# FPV_GROUND_STATION_SOURCE.net
KiCad netlist of a schematic drawn in EasyEDA Pro
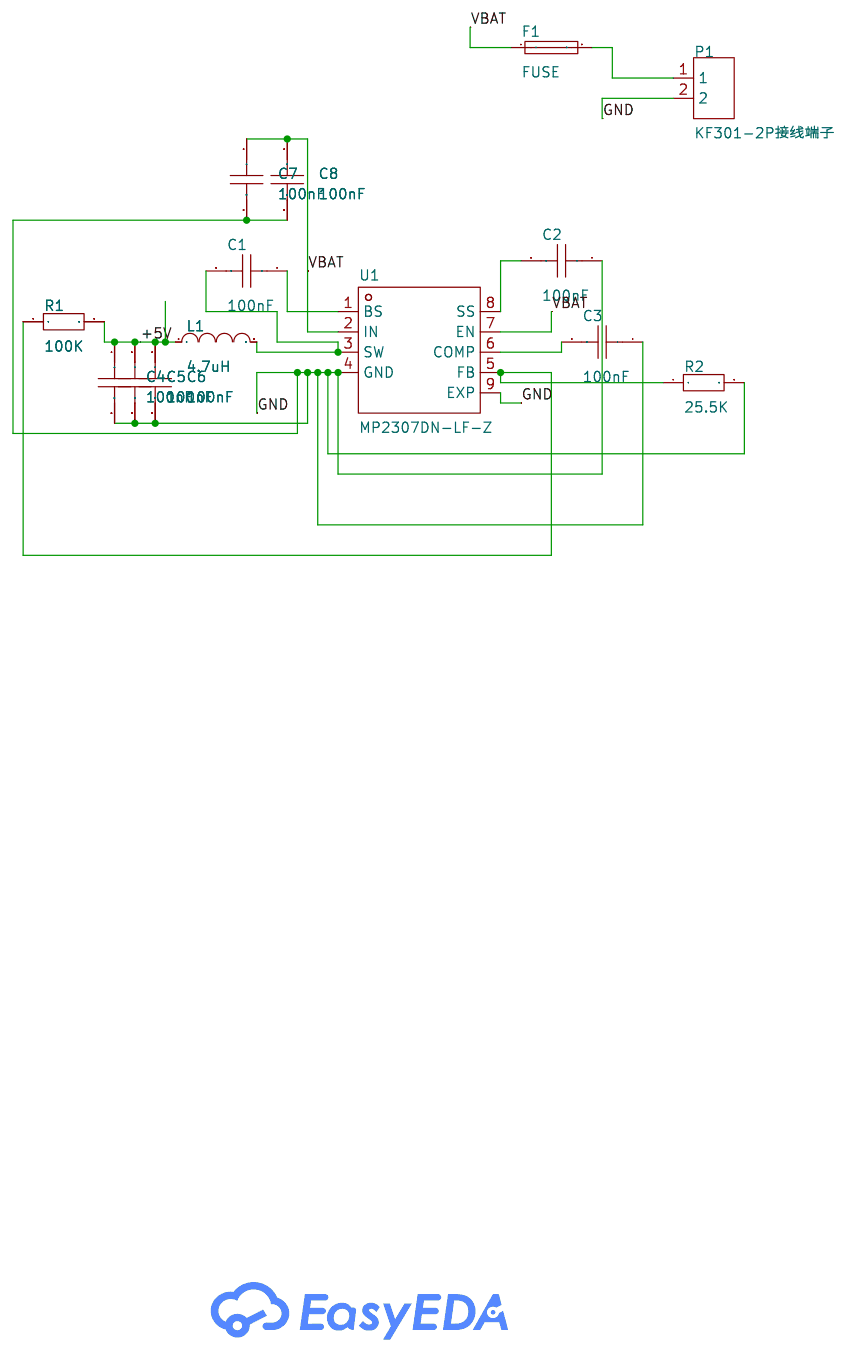
[diagram p0: POWER_BLK]
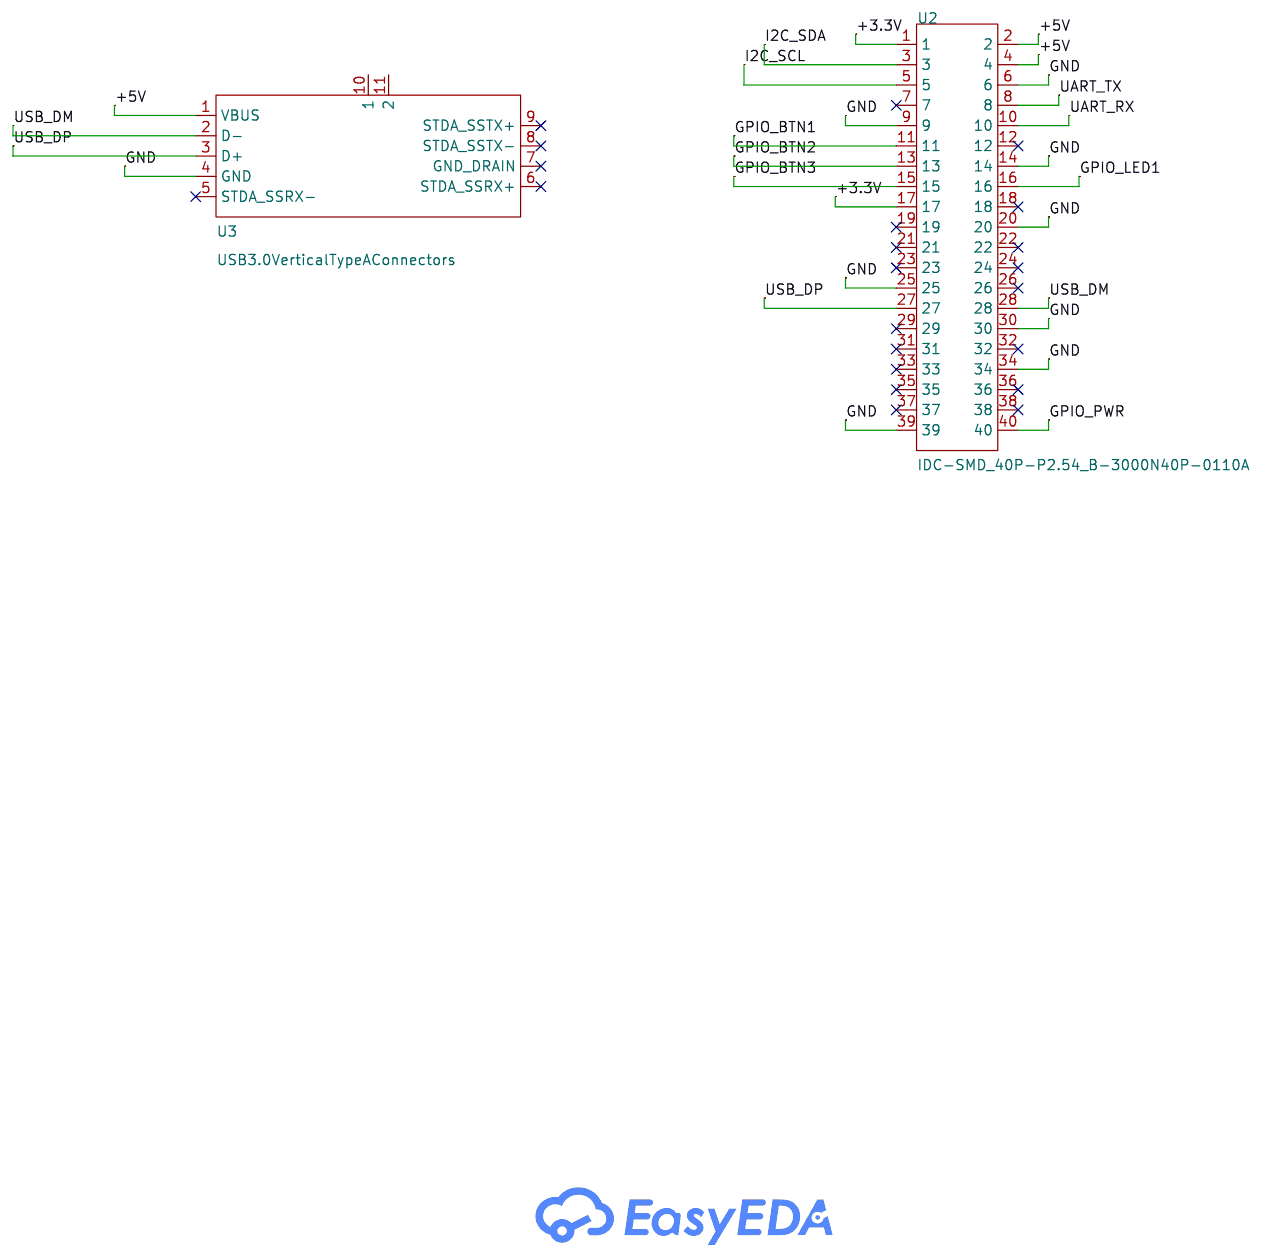
[diagram p1: GPIO header + USB-A]
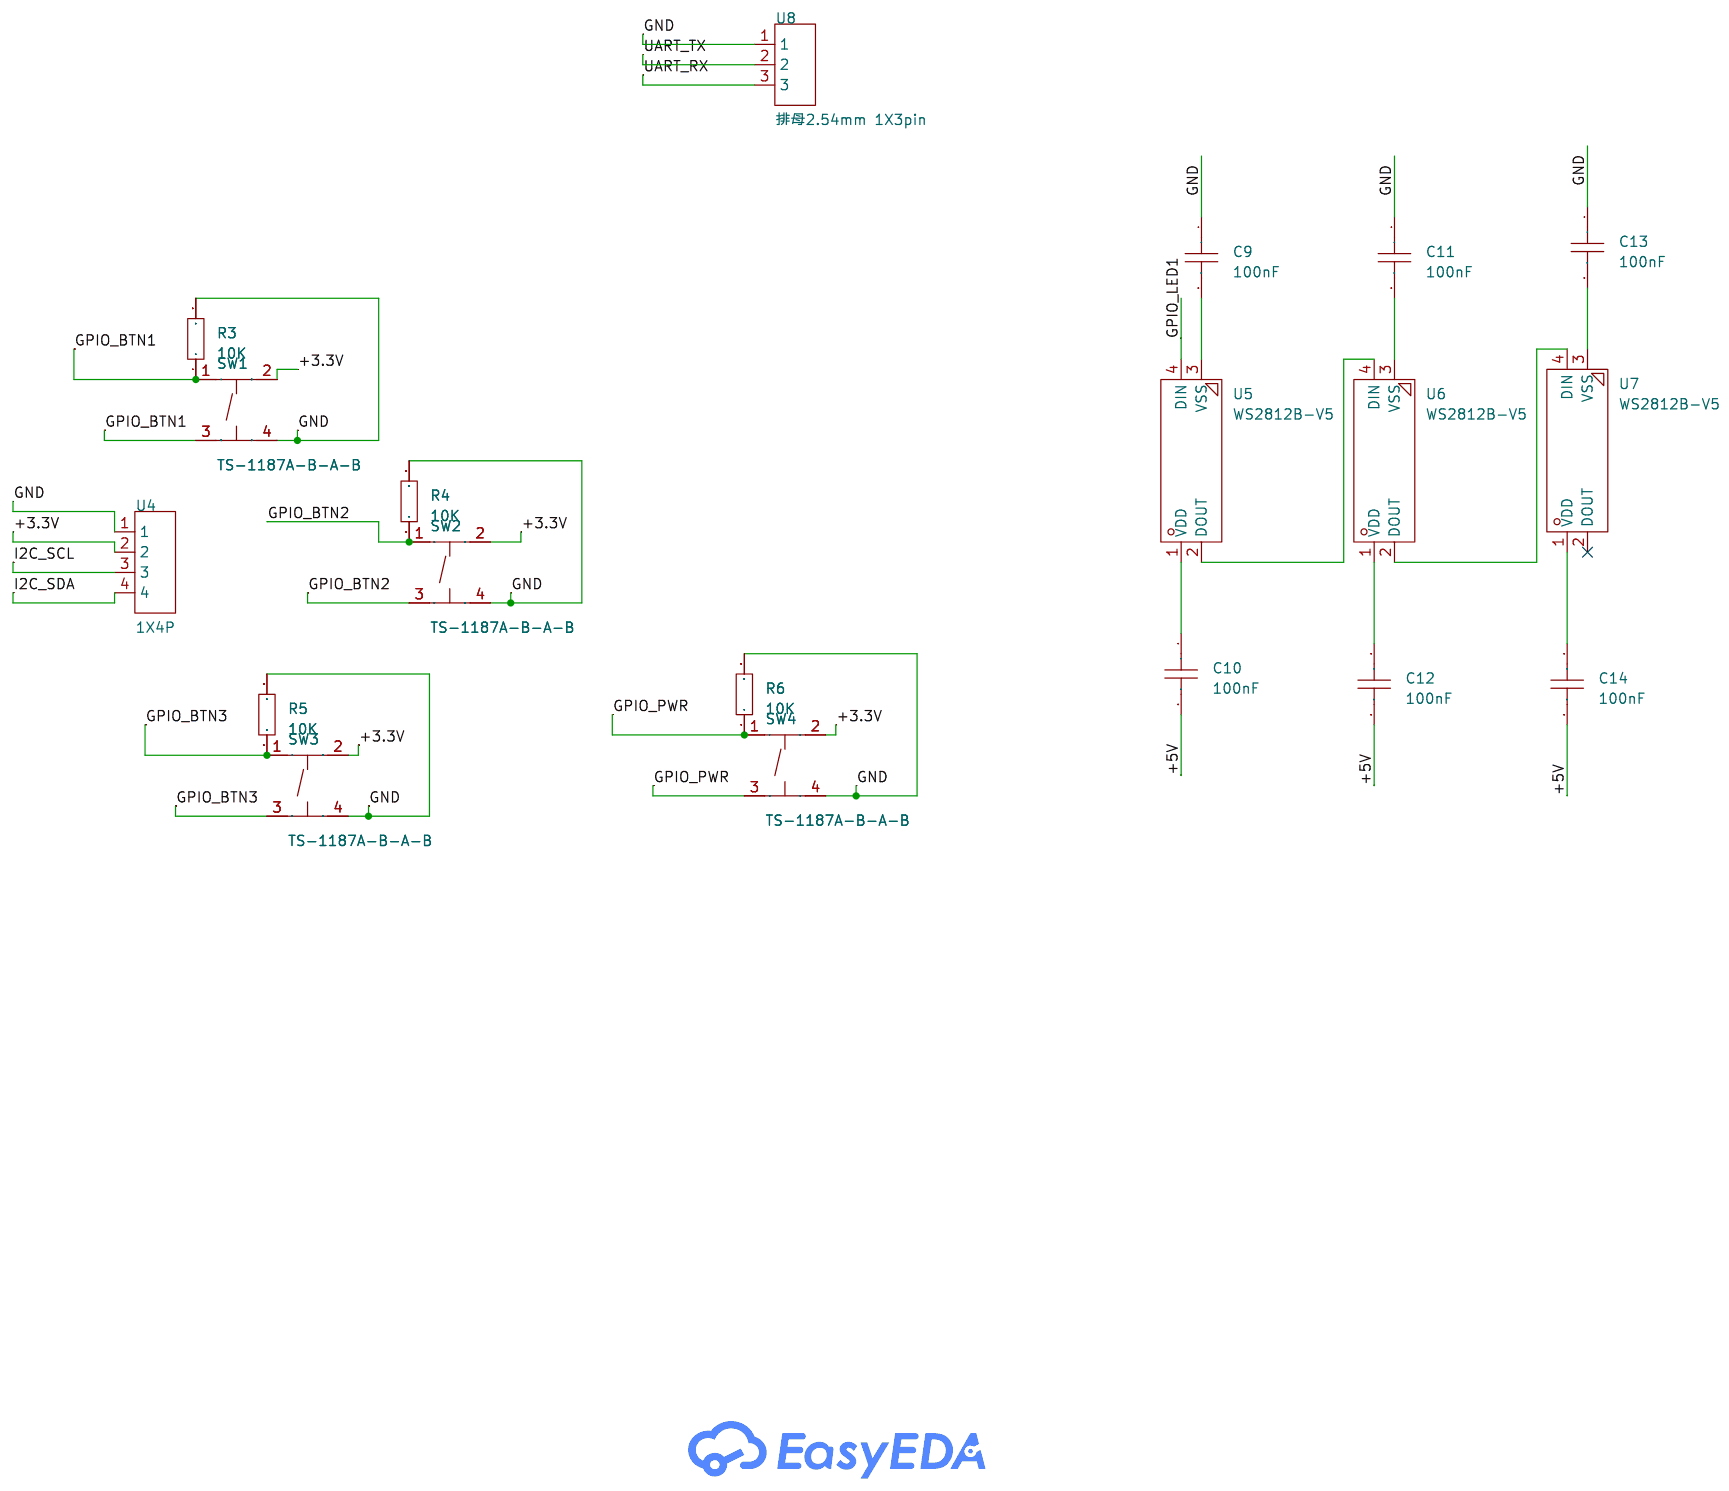
[diagram p2: LEDS AND OLED DISP]

(export (version "E")
  (design (tool "Eeschema 10.0.6"))
  (components
    (comp (ref "C1")
      (value "100nF")
      (footprint "easyedapro:C0603")
      (libsource (lib "easyedapro") (part "CAP"))
    )
    (comp (ref "C2")
      (value "100nF")
      (footprint "easyedapro:C0603")
      (libsource (lib "easyedapro") (part "CAP"))
    )
    (comp (ref "C3")
      (value "100nF")
      (footprint "easyedapro:C0603")
      (libsource (lib "easyedapro") (part "CAP"))
    )
    (comp (ref "C4")
      (value "100nF")
      (footprint "easyedapro:C0603")
      (libsource (lib "easyedapro") (part "CAP"))
    )
    (comp (ref "C5")
      (value "100nF")
      (footprint "easyedapro:C0603")
      (libsource (lib "easyedapro") (part "CAP"))
    )
    (comp (ref "C6")
      (value "100nF")
      (footprint "easyedapro:C0603")
      (libsource (lib "easyedapro") (part "CAP"))
    )
    (comp (ref "C7")
      (value "100nF")
      (footprint "easyedapro:C0603")
      (libsource (lib "easyedapro") (part "CAP"))
    )
    (comp (ref "C8")
      (value "100nF")
      (footprint "easyedapro:C0603")
      (libsource (lib "easyedapro") (part "CAP"))
    )
    (comp (ref "F1")
      (value "FUSE")
      (footprint "easyedapro:F1206")
      (libsource (lib "easyedapro") (part "FUSE"))
    )
    (comp (ref "L1")
      (value "4.7uH")
      (footprint "easyedapro:L0603")
      (libsource (lib "easyedapro") (part "电感"))
    )
    (comp (ref "P1")
      (value "KF301-2P接线端子")
      (footprint "easyedapro:CONN-TH_XY301V-A-5.0-2P")
      (libsource (lib "easyedapro") (part "KF301-2P接线端子"))
    )
    (comp (ref "R1")
      (value "100K")
      (footprint "easyedapro:R0603")
      (libsource (lib "easyedapro") (part "Res"))
    )
    (comp (ref "R2")
      (value "25.5K")
      (footprint "easyedapro:R0603")
      (libsource (lib "easyedapro") (part "Res"))
    )
    (comp (ref "U1")
      (value "MP2307DN-LF-Z")
      (footprint "easyedapro:SOP-8_L4.9-W3.9-P1.27-LS6.0-BL-EP")
      (fields (field (name "Manufacturer") "MPS(芯源)"))
      (libsource (lib "easyedapro") (part "MP2307DN-LF-Z"))
    )
    (comp (ref "U2")
      (value "IDC-SMD_40P-P2.54_B-3000N40P-0110A")
      (footprint "easyedapro:HDR-SMD_40P-P2.54-V-F-R2-C20-LS7.9")
      (libsource (lib "easyedapro") (part "IDC-SMD_40P-P2.54_B-3000N40P-0110A"))
    )
    (comp (ref "U3")
      (value "USB3.0VerticalTypeAConnectors")
      (footprint "easyedapro:USB-A-TH_C9900010398")
      (libsource (lib "easyedapro") (part "USB3.0VERTICALTYPEACONNECTORS"))
    )
    (comp (ref "C9")
      (value "100nF")
      (footprint "easyedapro:C0603")
      (libsource (lib "easyedapro") (part "CAP"))
    )
    (comp (ref "C10")
      (value "100nF")
      (footprint "easyedapro:C0603")
      (libsource (lib "easyedapro") (part "CAP"))
    )
    (comp (ref "C11")
      (value "100nF")
      (footprint "easyedapro:C0603")
      (libsource (lib "easyedapro") (part "CAP"))
    )
    (comp (ref "C12")
      (value "100nF")
      (footprint "easyedapro:C0603")
      (libsource (lib "easyedapro") (part "CAP"))
    )
    (comp (ref "C13")
      (value "100nF")
      (footprint "easyedapro:C0603")
      (libsource (lib "easyedapro") (part "CAP"))
    )
    (comp (ref "C14")
      (value "100nF")
      (footprint "easyedapro:C0603")
      (libsource (lib "easyedapro") (part "CAP"))
    )
    (comp (ref "R3") (value "10K") (footprint "easyedapro:R0603") (libsource (lib "easyedapro") (part "Res")))
    (comp (ref "R4") (value "10K") (footprint "easyedapro:R0603") (libsource (lib "easyedapro") (part "Res")))
    (comp (ref "R5") (value "10K") (footprint "easyedapro:R0603") (libsource (lib "easyedapro") (part "Res")))
    (comp (ref "R6") (value "10K") (footprint "easyedapro:R0603") (libsource (lib "easyedapro") (part "Res")))
    (comp (ref "SW1")
      (value "TS-1187A-B-A-B")
      (footprint "easyedapro:SW-SMD_4P-L5.1-W5.1-P3.70-LS6.5-TL_H1.5")
      (fields (field (name "Manufacturer") "XKB Connection(中国星坤)"))
      (libsource (lib "easyedapro") (part "TS-1187A-B-A-B"))
    )
    (comp (ref "SW2")
      (value "TS-1187A-B-A-B")
      (footprint "easyedapro:SW-SMD_4P-L5.1-W5.1-P3.70-LS6.5-TL_H1.5")
      (fields (field (name "Manufacturer") "XKB Connection(中国星坤)"))
      (libsource (lib "easyedapro") (part "TS-1187A-B-A-B"))
    )
    (comp (ref "SW3")
      (value "TS-1187A-B-A-B")
      (footprint "easyedapro:SW-SMD_4P-L5.1-W5.1-P3.70-LS6.5-TL_H1.5")
      (fields (field (name "Manufacturer") "XKB Connection(中国星坤)"))
      (libsource (lib "easyedapro") (part "TS-1187A-B-A-B"))
    )
    (comp (ref "SW4")
      (value "TS-1187A-B-A-B")
      (footprint "easyedapro:SW-SMD_4P-L5.1-W5.1-P3.70-LS6.5-TL_H1.5")
      (fields (field (name "Manufacturer") "XKB Connection(中国星坤)"))
      (libsource (lib "easyedapro") (part "TS-1187A-B-A-B"))
    )
    (comp (ref "U4")
      (value "1X4P")
      (footprint "easyedapro:CONN-TH_4P-P2.54_C9900022166")
      (libsource (lib "easyedapro") (part "1X4P"))
    )
    (comp (ref "U5")
      (value "WS2812B-V5")
      (footprint "easyedapro:LED-SMD_4P-L5.0-W5.0-TL_WS2812B-B")
      (libsource (lib "easyedapro") (part "WS2812B-V5"))
    )
    (comp (ref "U6")
      (value "WS2812B-V5")
      (footprint "easyedapro:LED-SMD_4P-L5.0-W5.0-TL_WS2812B-B")
      (libsource (lib "easyedapro") (part "WS2812B-V5"))
    )
    (comp (ref "U7")
      (value "WS2812B-V5")
      (footprint "easyedapro:LED-SMD_4P-L5.0-W5.0-TL_WS2812B-B")
      (libsource (lib "easyedapro") (part "WS2812B-V5"))
    )
    (comp (ref "U8")
      (value "排母2.54mm 1X3pin")
      (footprint "easyedapro:HDR-TH_3P-P2.54_CS-1165SDIG")
      (libsource (lib "easyedapro") (part "排母2.54MM 1X3PIN"))
    )
  )
  (nets
    (net (code "1") (name "+3.3V") (class "Default")
      (node (ref "SW1") (pin "2") (pinfunction "B_2") (pintype "unspecified"))
      (node (ref "SW2") (pin "2") (pinfunction "B_2") (pintype "unspecified"))
      (node (ref "SW3") (pin "2") (pinfunction "B_2") (pintype "unspecified"))
      (node (ref "SW4") (pin "2") (pinfunction "B_2") (pintype "unspecified"))
      (node (ref "U2") (pin "1") (pinfunction "1_1") (pintype "unspecified"))
      (node (ref "U2") (pin "17") (pinfunction "17_17") (pintype "unspecified"))
      (node (ref "U4") (pin "2") (pinfunction "2_2") (pintype "unspecified"))
    )
    (net (code "2") (name "+5V") (class "Default")
      (node (ref "C10") (pin "2") (pinfunction "2_2") (pintype "input"))
      (node (ref "C12") (pin "2") (pinfunction "2_2") (pintype "input"))
      (node (ref "C14") (pin "2") (pinfunction "2_2") (pintype "input"))
      (node (ref "C4") (pin "1") (pinfunction "1_1") (pintype "input"))
      (node (ref "C5") (pin "1") (pinfunction "1_1") (pintype "input"))
      (node (ref "C6") (pin "1") (pinfunction "1_1") (pintype "input"))
      (node (ref "L1") (pin "1") (pinfunction "1_1") (pintype "input"))
      (node (ref "R1") (pin "2") (pinfunction "2_2") (pintype "input"))
      (node (ref "U2") (pin "2") (pinfunction "2_2") (pintype "unspecified"))
      (node (ref "U2") (pin "4") (pinfunction "4_4") (pintype "unspecified"))
      (node (ref "U3") (pin "1") (pinfunction "VBUS_1") (pintype "unspecified"))
    )
    (net (code "3") (name "GND") (class "Default")
      (node (ref "C11") (pin "1") (pinfunction "1_1") (pintype "input"))
      (node (ref "C13") (pin "1") (pinfunction "1_1") (pintype "input"))
      (node (ref "C2") (pin "1") (pinfunction "1_1") (pintype "input"))
      (node (ref "C3") (pin "1") (pinfunction "1_1") (pintype "input"))
      (node (ref "C4") (pin "2") (pinfunction "2_2") (pintype "input"))
      (node (ref "C5") (pin "2") (pinfunction "2_2") (pintype "input"))
      (node (ref "C6") (pin "2") (pinfunction "2_2") (pintype "input"))
      (node (ref "C7") (pin "2") (pinfunction "2_2") (pintype "input"))
      (node (ref "C8") (pin "2") (pinfunction "2_2") (pintype "input"))
      (node (ref "C9") (pin "1") (pinfunction "1_1") (pintype "input"))
      (node (ref "P1") (pin "2") (pinfunction "2_2") (pintype "unspecified"))
      (node (ref "R2") (pin "2") (pinfunction "2_2") (pintype "input"))
      (node (ref "R3") (pin "2") (pinfunction "2_2") (pintype "input"))
      (node (ref "R4") (pin "2") (pinfunction "2_2") (pintype "input"))
      (node (ref "R5") (pin "2") (pinfunction "2_2") (pintype "input"))
      (node (ref "R6") (pin "2") (pinfunction "2_2") (pintype "input"))
      (node (ref "SW1") (pin "4") (pinfunction "D_4") (pintype "unspecified"))
      (node (ref "SW2") (pin "4") (pinfunction "D_4") (pintype "unspecified"))
      (node (ref "SW3") (pin "4") (pinfunction "D_4") (pintype "unspecified"))
      (node (ref "SW4") (pin "4") (pinfunction "D_4") (pintype "unspecified"))
      (node (ref "U1") (pin "4") (pinfunction "GND_4") (pintype "unspecified"))
      (node (ref "U1") (pin "9") (pinfunction "EXP_9") (pintype "unspecified"))
      (node (ref "U2") (pin "14") (pinfunction "14_14") (pintype "unspecified"))
      (node (ref "U2") (pin "20") (pinfunction "20_20") (pintype "unspecified"))
      (node (ref "U2") (pin "25") (pinfunction "25_25") (pintype "unspecified"))
      (node (ref "U2") (pin "30") (pinfunction "30_30") (pintype "unspecified"))
      (node (ref "U2") (pin "34") (pinfunction "34_34") (pintype "unspecified"))
      (node (ref "U2") (pin "39") (pinfunction "39_39") (pintype "unspecified"))
      (node (ref "U2") (pin "6") (pinfunction "6_6") (pintype "unspecified"))
      (node (ref "U2") (pin "9") (pinfunction "9_9") (pintype "unspecified"))
      (node (ref "U3") (pin "4") (pinfunction "GND_4") (pintype "unspecified"))
      (node (ref "U4") (pin "1") (pinfunction "1_1") (pintype "unspecified"))
      (node (ref "U8") (pin "1") (pinfunction "1_1") (pintype "unspecified"))
    )
    (net (code "4") (name "GPIO_BTN1") (class "Default")
      (node (ref "R3") (pin "1") (pinfunction "1_1") (pintype "input"))
      (node (ref "SW1") (pin "1") (pinfunction "A_1") (pintype "unspecified"))
      (node (ref "SW1") (pin "3") (pinfunction "C_3") (pintype "unspecified"))
      (node (ref "U2") (pin "11") (pinfunction "11_11") (pintype "unspecified"))
    )
    (net (code "5") (name "GPIO_BTN2") (class "Default")
      (node (ref "R4") (pin "1") (pinfunction "1_1") (pintype "input"))
      (node (ref "SW2") (pin "1") (pinfunction "A_1") (pintype "unspecified"))
      (node (ref "SW2") (pin "3") (pinfunction "C_3") (pintype "unspecified"))
      (node (ref "U2") (pin "13") (pinfunction "13_13") (pintype "unspecified"))
    )
    (net (code "6") (name "GPIO_BTN3") (class "Default")
      (node (ref "R5") (pin "1") (pinfunction "1_1") (pintype "input"))
      (node (ref "SW3") (pin "1") (pinfunction "A_1") (pintype "unspecified"))
      (node (ref "SW3") (pin "3") (pinfunction "C_3") (pintype "unspecified"))
      (node (ref "U2") (pin "15") (pinfunction "15_15") (pintype "unspecified"))
    )
    (net (code "7") (name "GPIO_LED1") (class "Default")
      (node (ref "U2") (pin "16") (pinfunction "16_16") (pintype "unspecified"))
      (node (ref "U5") (pin "4") (pinfunction "DIN_4") (pintype "unspecified"))
    )
    (net (code "8") (name "GPIO_PWR") (class "Default")
      (node (ref "R6") (pin "1") (pinfunction "1_1") (pintype "input"))
      (node (ref "SW4") (pin "1") (pinfunction "A_1") (pintype "unspecified"))
      (node (ref "SW4") (pin "3") (pinfunction "C_3") (pintype "unspecified"))
      (node (ref "U2") (pin "40") (pinfunction "40_40") (pintype "unspecified"))
    )
    (net (code "9") (name "I2C_SCL") (class "Default")
      (node (ref "U2") (pin "5") (pinfunction "5_5") (pintype "unspecified"))
      (node (ref "U4") (pin "3") (pinfunction "3_3") (pintype "unspecified"))
    )
    (net (code "10") (name "I2C_SDA") (class "Default")
      (node (ref "U2") (pin "3") (pinfunction "3_3") (pintype "unspecified"))
      (node (ref "U4") (pin "4") (pinfunction "4_4") (pintype "unspecified"))
    )
    (net (code "11") (name "Net-(F1-Pad2)") (class "Default")
      (node (ref "F1") (pin "2") (pinfunction "2_2") (pintype "unspecified"))
      (node (ref "P1") (pin "1") (pinfunction "1_1") (pintype "unspecified"))
    )
    (net (code "12") (name "Net-(U1-BS)") (class "Default")
      (node (ref "C1") (pin "1") (pinfunction "1_1") (pintype "input"))
      (node (ref "U1") (pin "1") (pinfunction "BS_1") (pintype "unspecified"))
    )
    (net (code "13") (name "Net-(U1-COMP)") (class "Default")
      (node (ref "C3") (pin "2") (pinfunction "2_2") (pintype "input"))
      (node (ref "U1") (pin "6") (pinfunction "COMP_6") (pintype "unspecified"))
    )
    (net (code "14") (name "Net-(U1-FB)") (class "Default")
      (node (ref "R1") (pin "1") (pinfunction "1_1") (pintype "input"))
      (node (ref "R2") (pin "1") (pinfunction "1_1") (pintype "input"))
      (node (ref "U1") (pin "5") (pinfunction "FB_5") (pintype "unspecified"))
    )
    (net (code "15") (name "Net-(U1-SS)") (class "Default")
      (node (ref "C2") (pin "2") (pinfunction "2_2") (pintype "input"))
      (node (ref "U1") (pin "8") (pinfunction "SS_8") (pintype "unspecified"))
    )
    (net (code "16") (name "Net-(U1-SW)") (class "Default")
      (node (ref "C1") (pin "2") (pinfunction "2_2") (pintype "input"))
      (node (ref "L1") (pin "2") (pinfunction "2_2") (pintype "input"))
      (node (ref "U1") (pin "3") (pinfunction "SW_3") (pintype "unspecified"))
    )
    (net (code "17") (name "Net-(U5-DOUT)") (class "Default")
      (node (ref "U5") (pin "2") (pinfunction "DOUT_2") (pintype "unspecified"))
      (node (ref "U6") (pin "4") (pinfunction "DIN_4") (pintype "unspecified"))
    )
    (net (code "18") (name "Net-(U5-VDD)") (class "Default")
      (node (ref "C10") (pin "1") (pinfunction "1_1") (pintype "input"))
      (node (ref "U5") (pin "1") (pinfunction "VDD_1") (pintype "unspecified"))
    )
    (net (code "19") (name "Net-(U5-VSS)") (class "Default")
      (node (ref "C9") (pin "2") (pinfunction "2_2") (pintype "input"))
      (node (ref "U5") (pin "3") (pinfunction "VSS_3") (pintype "unspecified"))
    )
    (net (code "20") (name "Net-(U6-DOUT)") (class "Default")
      (node (ref "U6") (pin "2") (pinfunction "DOUT_2") (pintype "unspecified"))
      (node (ref "U7") (pin "4") (pinfunction "DIN_4") (pintype "unspecified"))
    )
    (net (code "21") (name "Net-(U6-VDD)") (class "Default")
      (node (ref "C12") (pin "1") (pinfunction "1_1") (pintype "input"))
      (node (ref "U6") (pin "1") (pinfunction "VDD_1") (pintype "unspecified"))
    )
    (net (code "22") (name "Net-(U6-VSS)") (class "Default")
      (node (ref "C11") (pin "2") (pinfunction "2_2") (pintype "input"))
      (node (ref "U6") (pin "3") (pinfunction "VSS_3") (pintype "unspecified"))
    )
    (net (code "23") (name "Net-(U7-VDD)") (class "Default")
      (node (ref "C14") (pin "1") (pinfunction "1_1") (pintype "input"))
      (node (ref "U7") (pin "1") (pinfunction "VDD_1") (pintype "unspecified"))
    )
    (net (code "24") (name "Net-(U7-VSS)") (class "Default")
      (node (ref "C13") (pin "2") (pinfunction "2_2") (pintype "input"))
      (node (ref "U7") (pin "3") (pinfunction "VSS_3") (pintype "unspecified"))
    )
    (net (code "25") (name "UART_RX") (class "Default")
      (node (ref "U2") (pin "10") (pinfunction "10_10") (pintype "unspecified"))
      (node (ref "U8") (pin "3") (pinfunction "3_3") (pintype "unspecified"))
    )
    (net (code "26") (name "UART_TX") (class "Default")
      (node (ref "U2") (pin "8") (pinfunction "8_8") (pintype "unspecified"))
      (node (ref "U8") (pin "2") (pinfunction "2_2") (pintype "unspecified"))
    )
    (net (code "27") (name "USB_DM") (class "Default")
      (node (ref "U2") (pin "28") (pinfunction "28_28") (pintype "unspecified"))
      (node (ref "U3") (pin "2") (pinfunction "D-_2") (pintype "unspecified"))
    )
    (net (code "28") (name "USB_DP") (class "Default")
      (node (ref "U2") (pin "27") (pinfunction "27_27") (pintype "unspecified"))
      (node (ref "U3") (pin "3") (pinfunction "D+_3") (pintype "unspecified"))
    )
    (net (code "29") (name "VBAT") (class "Default")
      (node (ref "C7") (pin "1") (pinfunction "1_1") (pintype "input"))
      (node (ref "C8") (pin "1") (pinfunction "1_1") (pintype "input"))
      (node (ref "F1") (pin "1") (pinfunction "1_1") (pintype "unspecified"))
      (node (ref "U1") (pin "2") (pinfunction "IN_2") (pintype "unspecified"))
      (node (ref "U1") (pin "7") (pinfunction "EN_7") (pintype "unspecified"))
    )
    (net (code "30") (name "unconnected-(U2-Pad7)") (class "Default")
      (node (ref "U2") (pin "7") (pinfunction "7_7") (pintype "unspecified+no_connect"))
    )
    (net (code "31") (name "unconnected-(U2-Pad12)") (class "Default")
      (node (ref "U2") (pin "12") (pinfunction "12_12") (pintype "unspecified+no_connect"))
    )
    (net (code "32") (name "unconnected-(U2-Pad18)") (class "Default")
      (node (ref "U2") (pin "18") (pinfunction "18_18") (pintype "unspecified+no_connect"))
    )
    (net (code "33") (name "unconnected-(U2-Pad19)") (class "Default")
      (node (ref "U2") (pin "19") (pinfunction "19_19") (pintype "unspecified+no_connect"))
    )
    (net (code "34") (name "unconnected-(U2-Pad21)") (class "Default")
      (node (ref "U2") (pin "21") (pinfunction "21_21") (pintype "unspecified+no_connect"))
    )
    (net (code "35") (name "unconnected-(U2-Pad22)") (class "Default")
      (node (ref "U2") (pin "22") (pinfunction "22_22") (pintype "unspecified+no_connect"))
    )
    (net (code "36") (name "unconnected-(U2-Pad23)") (class "Default")
      (node (ref "U2") (pin "23") (pinfunction "23_23") (pintype "unspecified+no_connect"))
    )
    (net (code "37") (name "unconnected-(U2-Pad24)") (class "Default")
      (node (ref "U2") (pin "24") (pinfunction "24_24") (pintype "unspecified+no_connect"))
    )
    (net (code "38") (name "unconnected-(U2-Pad26)") (class "Default")
      (node (ref "U2") (pin "26") (pinfunction "26_26") (pintype "unspecified+no_connect"))
    )
    (net (code "39") (name "unconnected-(U2-Pad29)") (class "Default")
      (node (ref "U2") (pin "29") (pinfunction "29_29") (pintype "unspecified+no_connect"))
    )
    (net (code "40") (name "unconnected-(U2-Pad31)") (class "Default")
      (node (ref "U2") (pin "31") (pinfunction "31_31") (pintype "unspecified+no_connect"))
    )
    (net (code "41") (name "unconnected-(U2-Pad32)") (class "Default")
      (node (ref "U2") (pin "32") (pinfunction "32_32") (pintype "unspecified+no_connect"))
    )
    (net (code "42") (name "unconnected-(U2-Pad33)") (class "Default")
      (node (ref "U2") (pin "33") (pinfunction "33_33") (pintype "unspecified+no_connect"))
    )
    (net (code "43") (name "unconnected-(U2-Pad35)") (class "Default")
      (node (ref "U2") (pin "35") (pinfunction "35_35") (pintype "unspecified+no_connect"))
    )
    (net (code "44") (name "unconnected-(U2-Pad36)") (class "Default")
      (node (ref "U2") (pin "36") (pinfunction "36_36") (pintype "unspecified+no_connect"))
    )
    (net (code "45") (name "unconnected-(U2-Pad37)") (class "Default")
      (node (ref "U2") (pin "37") (pinfunction "37_37") (pintype "unspecified+no_connect"))
    )
    (net (code "46") (name "unconnected-(U2-Pad38)") (class "Default")
      (node (ref "U2") (pin "38") (pinfunction "38_38") (pintype "unspecified+no_connect"))
    )
    (net (code "47") (name "unconnected-(U3-1-Pad10)") (class "Default")
      (node (ref "U3") (pin "10") (pinfunction "1_10") (pintype "unspecified"))
    )
    (net (code "48") (name "unconnected-(U3-2-Pad11)") (class "Default")
      (node (ref "U3") (pin "11") (pinfunction "2_11") (pintype "unspecified"))
    )
    (net (code "49") (name "unconnected-(U3-GND_DRAIN-Pad7)") (class "Default")
      (node (ref "U3") (pin "7") (pinfunction "GND_DRAIN_7") (pintype "unspecified+no_connect"))
    )
    (net (code "50") (name "unconnected-(U3-STDA_SSRX+-Pad6)") (class "Default")
      (node (ref "U3") (pin "6") (pinfunction "STDA_SSRX+_6") (pintype "unspecified+no_connect"))
    )
    (net (code "51") (name "unconnected-(U3-STDA_SSRX--Pad5)") (class "Default")
      (node (ref "U3") (pin "5") (pinfunction "STDA_SSRX-_5") (pintype "unspecified+no_connect"))
    )
    (net (code "52") (name "unconnected-(U3-STDA_SSTX+-Pad9)") (class "Default")
      (node (ref "U3") (pin "9") (pinfunction "STDA_SSTX+_9") (pintype "unspecified+no_connect"))
    )
    (net (code "53") (name "unconnected-(U3-STDA_SSTX--Pad8)") (class "Default")
      (node (ref "U3") (pin "8") (pinfunction "STDA_SSTX-_8") (pintype "unspecified+no_connect"))
    )
    (net (code "54") (name "unconnected-(U7-DOUT-Pad2)") (class "Default")
      (node (ref "U7") (pin "2") (pinfunction "DOUT_2") (pintype "unspecified+no_connect"))
    )
  )
)
